# diff-probe.net
KiCad netlist of a schematic drawn in EAGLE
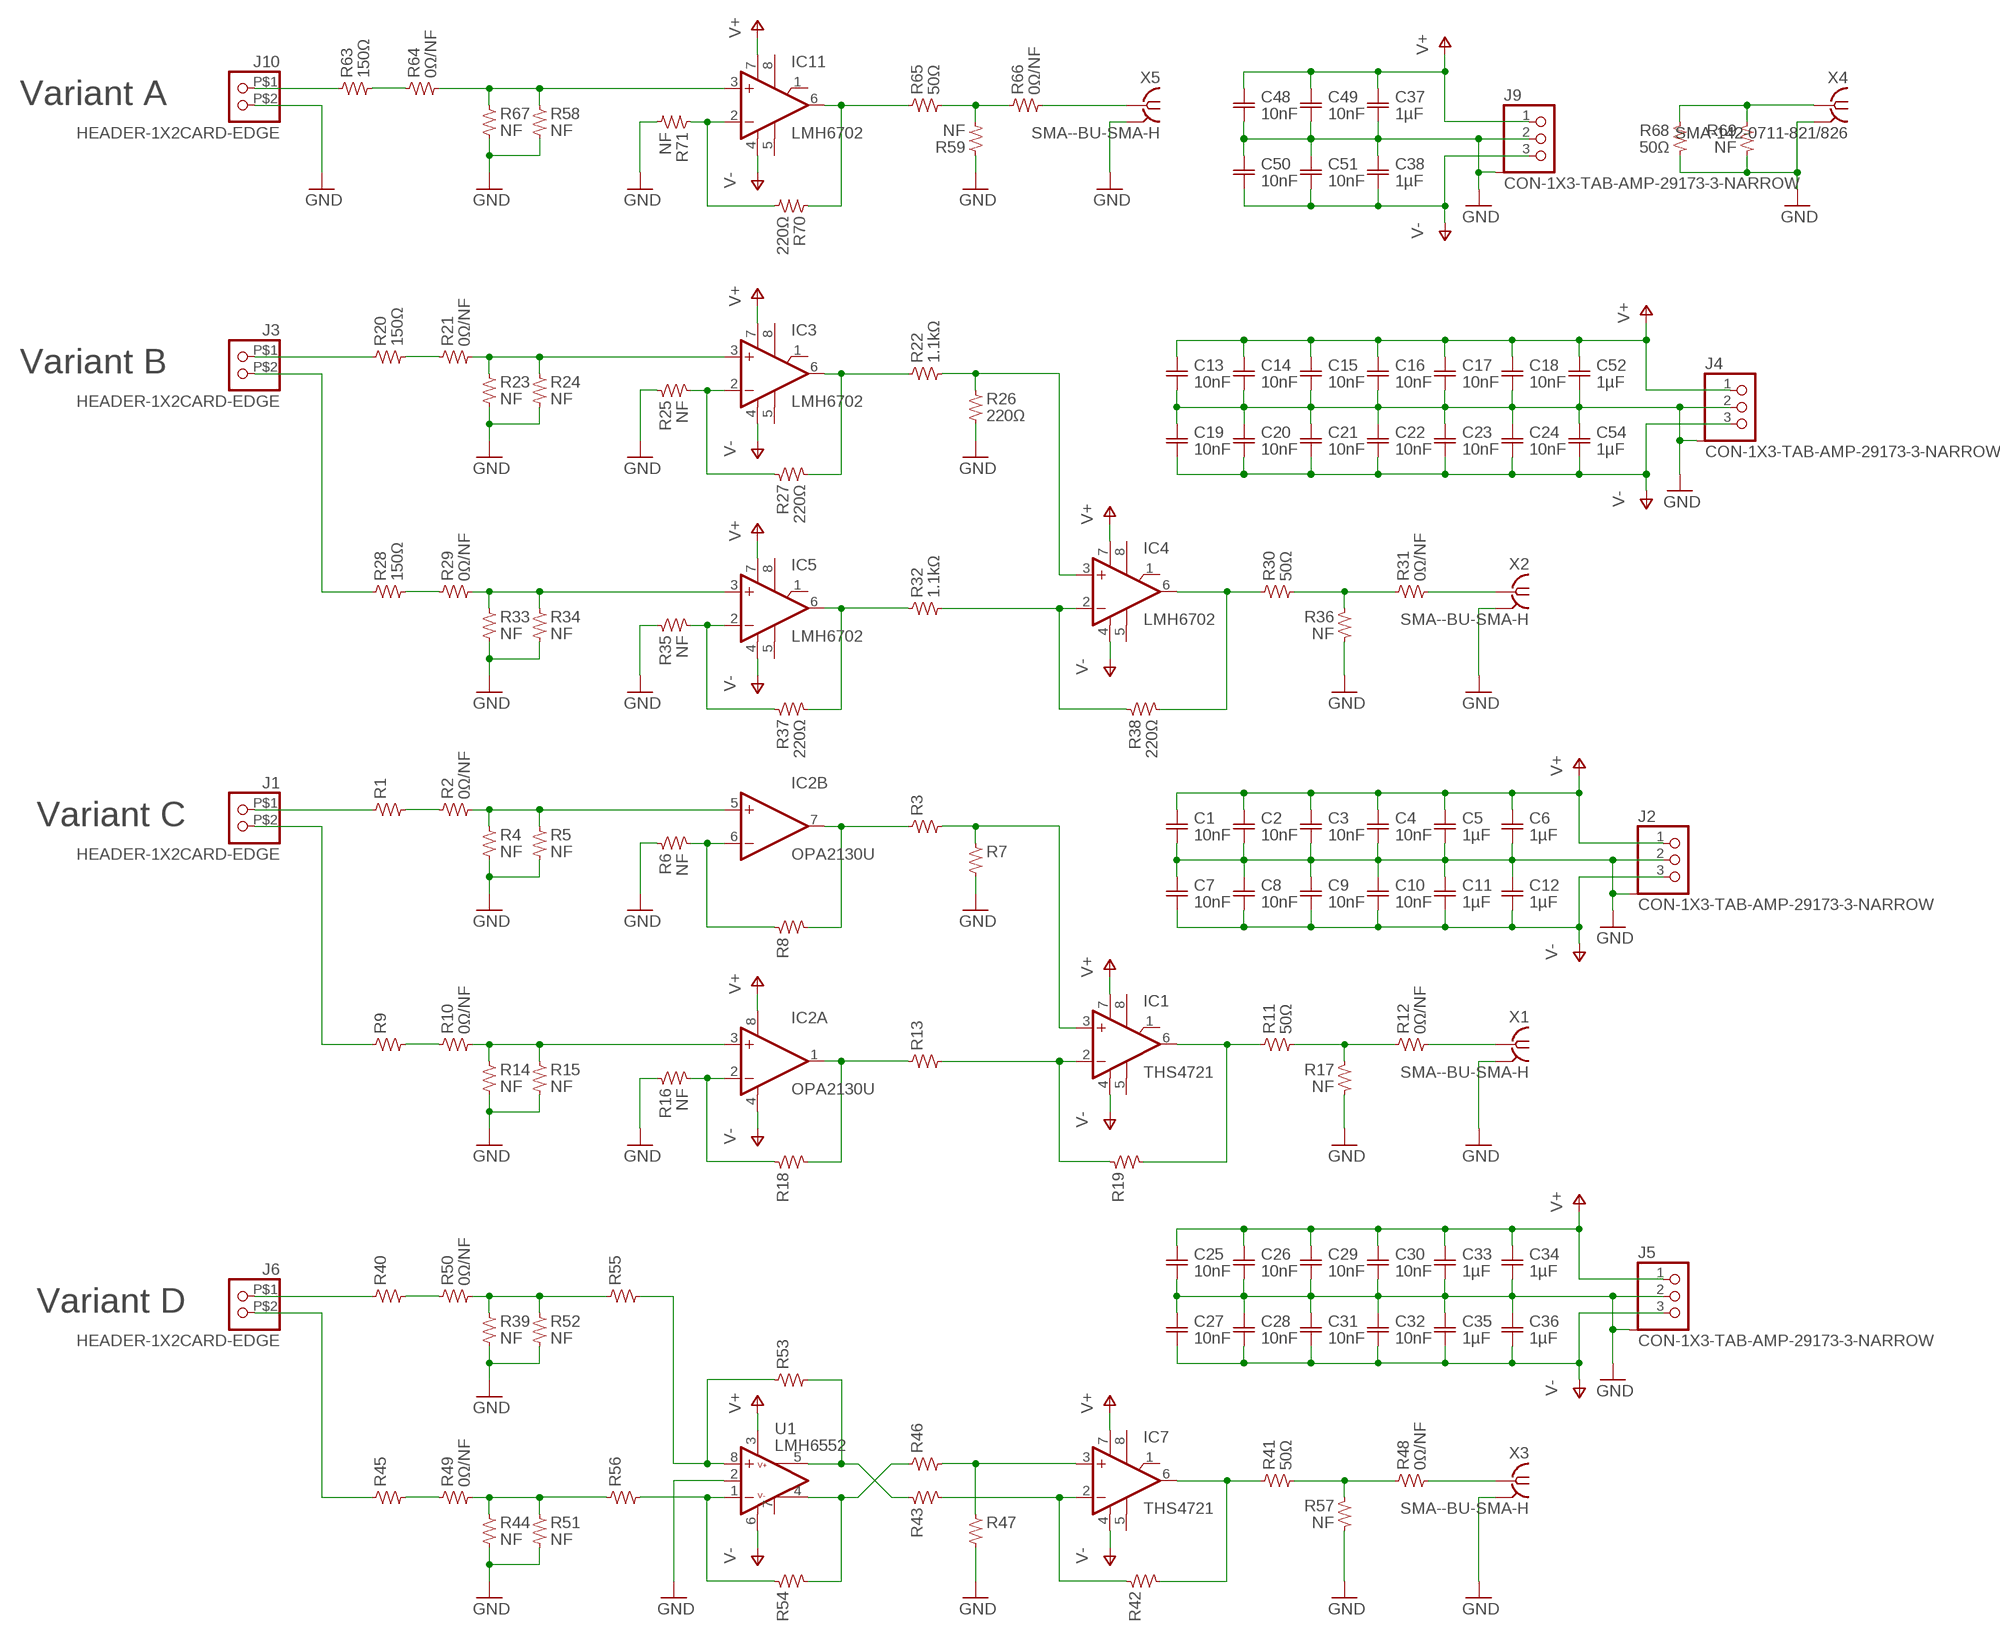
[diagram p0: schematic, sheet 1]

(export (version "E")
  (design (tool "Eeschema 10.0.6"))
  (components
    (comp (ref "C1")
      (value "10nF")
      (footprint "eagle-import:0402-SQUARE")
      (libsource (lib "eagle-import") (part "C-EU-0402-SQUARE"))
    )
    (comp (ref "C2")
      (value "10nF")
      (footprint "eagle-import:0402-SQUARE")
      (libsource (lib "eagle-import") (part "C-EU-0402-SQUARE"))
    )
    (comp (ref "C3")
      (value "10nF")
      (footprint "eagle-import:0402-SQUARE")
      (libsource (lib "eagle-import") (part "C-EU-0402-SQUARE"))
    )
    (comp (ref "C4")
      (value "10nF")
      (footprint "eagle-import:0402-SQUARE")
      (libsource (lib "eagle-import") (part "C-EU-0402-SQUARE"))
    )
    (comp (ref "C5")
      (value "1µF")
      (footprint "eagle-import:0603-SQUARE")
      (libsource (lib "eagle-import") (part "C-EU-0603-SQUARE"))
    )
    (comp (ref "C6")
      (value "1µF")
      (footprint "eagle-import:0603-SQUARE")
      (libsource (lib "eagle-import") (part "C-EU-0603-SQUARE"))
    )
    (comp (ref "C7")
      (value "10nF")
      (footprint "eagle-import:0402-SQUARE")
      (libsource (lib "eagle-import") (part "C-EU-0402-SQUARE"))
    )
    (comp (ref "C8")
      (value "10nF")
      (footprint "eagle-import:0402-SQUARE")
      (libsource (lib "eagle-import") (part "C-EU-0402-SQUARE"))
    )
    (comp (ref "C9")
      (value "10nF")
      (footprint "eagle-import:0402-SQUARE")
      (libsource (lib "eagle-import") (part "C-EU-0402-SQUARE"))
    )
    (comp (ref "C10")
      (value "10nF")
      (footprint "eagle-import:0402-SQUARE")
      (libsource (lib "eagle-import") (part "C-EU-0402-SQUARE"))
    )
    (comp (ref "C11")
      (value "1µF")
      (footprint "eagle-import:0603-SQUARE")
      (libsource (lib "eagle-import") (part "C-EU-0603-SQUARE"))
    )
    (comp (ref "C12")
      (value "1µF")
      (footprint "eagle-import:0603-SQUARE")
      (libsource (lib "eagle-import") (part "C-EU-0603-SQUARE"))
    )
    (comp (ref "C13")
      (value "10nF")
      (footprint "eagle-import:0402-SQUARE")
      (libsource (lib "eagle-import") (part "C-EU-0402-SQUARE"))
    )
    (comp (ref "C14")
      (value "10nF")
      (footprint "eagle-import:0402-SQUARE")
      (libsource (lib "eagle-import") (part "C-EU-0402-SQUARE"))
    )
    (comp (ref "C15")
      (value "10nF")
      (footprint "eagle-import:0402-SQUARE")
      (libsource (lib "eagle-import") (part "C-EU-0402-SQUARE"))
    )
    (comp (ref "C16")
      (value "10nF")
      (footprint "eagle-import:0402-SQUARE")
      (libsource (lib "eagle-import") (part "C-EU-0402-SQUARE"))
    )
    (comp (ref "C17")
      (value "10nF")
      (footprint "eagle-import:0402-SQUARE")
      (libsource (lib "eagle-import") (part "C-EU-0402-SQUARE"))
    )
    (comp (ref "C18")
      (value "10nF")
      (footprint "eagle-import:0402-SQUARE")
      (libsource (lib "eagle-import") (part "C-EU-0402-SQUARE"))
    )
    (comp (ref "C19")
      (value "10nF")
      (footprint "eagle-import:0402-SQUARE")
      (libsource (lib "eagle-import") (part "C-EU-0402-SQUARE"))
    )
    (comp (ref "C20")
      (value "10nF")
      (footprint "eagle-import:0402-SQUARE")
      (libsource (lib "eagle-import") (part "C-EU-0402-SQUARE"))
    )
    (comp (ref "C21")
      (value "10nF")
      (footprint "eagle-import:0402-SQUARE")
      (libsource (lib "eagle-import") (part "C-EU-0402-SQUARE"))
    )
    (comp (ref "C22")
      (value "10nF")
      (footprint "eagle-import:0402-SQUARE")
      (libsource (lib "eagle-import") (part "C-EU-0402-SQUARE"))
    )
    (comp (ref "C23")
      (value "10nF")
      (footprint "eagle-import:0402-SQUARE")
      (libsource (lib "eagle-import") (part "C-EU-0402-SQUARE"))
    )
    (comp (ref "C24")
      (value "10nF")
      (footprint "eagle-import:0402-SQUARE")
      (libsource (lib "eagle-import") (part "C-EU-0402-SQUARE"))
    )
    (comp (ref "C25")
      (value "10nF")
      (footprint "eagle-import:0402-SQUARE")
      (libsource (lib "eagle-import") (part "C-EU-0402-SQUARE"))
    )
    (comp (ref "C26")
      (value "10nF")
      (footprint "eagle-import:0402-SQUARE")
      (libsource (lib "eagle-import") (part "C-EU-0402-SQUARE"))
    )
    (comp (ref "C27")
      (value "10nF")
      (footprint "eagle-import:0402-SQUARE")
      (libsource (lib "eagle-import") (part "C-EU-0402-SQUARE"))
    )
    (comp (ref "C28")
      (value "10nF")
      (footprint "eagle-import:0402-SQUARE")
      (libsource (lib "eagle-import") (part "C-EU-0402-SQUARE"))
    )
    (comp (ref "C29")
      (value "10nF")
      (footprint "eagle-import:0402-SQUARE")
      (libsource (lib "eagle-import") (part "C-EU-0402-SQUARE"))
    )
    (comp (ref "C30")
      (value "10nF")
      (footprint "eagle-import:0402-SQUARE")
      (libsource (lib "eagle-import") (part "C-EU-0402-SQUARE"))
    )
    (comp (ref "C31")
      (value "10nF")
      (footprint "eagle-import:0402-SQUARE")
      (libsource (lib "eagle-import") (part "C-EU-0402-SQUARE"))
    )
    (comp (ref "C32")
      (value "10nF")
      (footprint "eagle-import:0402-SQUARE")
      (libsource (lib "eagle-import") (part "C-EU-0402-SQUARE"))
    )
    (comp (ref "C33")
      (value "1µF")
      (footprint "eagle-import:0603-SQUARE")
      (libsource (lib "eagle-import") (part "C-EU-0603-SQUARE"))
    )
    (comp (ref "C34")
      (value "1µF")
      (footprint "eagle-import:0603-SQUARE")
      (libsource (lib "eagle-import") (part "C-EU-0603-SQUARE"))
    )
    (comp (ref "C35")
      (value "1µF")
      (footprint "eagle-import:0603-SQUARE")
      (libsource (lib "eagle-import") (part "C-EU-0603-SQUARE"))
    )
    (comp (ref "C36")
      (value "1µF")
      (footprint "eagle-import:0603-SQUARE")
      (libsource (lib "eagle-import") (part "C-EU-0603-SQUARE"))
    )
    (comp (ref "C37")
      (value "1µF")
      (footprint "eagle-import:0603-SQUARE")
      (libsource (lib "eagle-import") (part "C-EU-0603-SQUARE"))
    )
    (comp (ref "C38")
      (value "1µF")
      (footprint "eagle-import:0603-SQUARE")
      (libsource (lib "eagle-import") (part "C-EU-0603-SQUARE"))
    )
    (comp (ref "C48")
      (value "10nF")
      (footprint "eagle-import:0402-SQUARE")
      (libsource (lib "eagle-import") (part "C-EU-0402-SQUARE"))
    )
    (comp (ref "C49")
      (value "10nF")
      (footprint "eagle-import:0402-SQUARE")
      (libsource (lib "eagle-import") (part "C-EU-0402-SQUARE"))
    )
    (comp (ref "C50")
      (value "10nF")
      (footprint "eagle-import:0402-SQUARE")
      (libsource (lib "eagle-import") (part "C-EU-0402-SQUARE"))
    )
    (comp (ref "C51")
      (value "10nF")
      (footprint "eagle-import:0402-SQUARE")
      (libsource (lib "eagle-import") (part "C-EU-0402-SQUARE"))
    )
    (comp (ref "C52")
      (value "1µF")
      (footprint "eagle-import:0603")
      (libsource (lib "eagle-import") (part "C-EU-0603"))
    )
    (comp (ref "C54")
      (value "1µF")
      (footprint "eagle-import:0603")
      (libsource (lib "eagle-import") (part "C-EU-0603"))
    )
    (comp (ref "IC1")
      (value "THS4721")
      (footprint "eagle-import:SO08")
      (fields (field (name "MPN") "AD9631ARZ"))
      (libsource (lib "eagle-import") (part "OP-AMP-8-TI"))
    )
    (comp (ref "IC2")
      (value "OPA2130U")
      (footprint "eagle-import:SO08")
      (fields (field (name "MF") "TEXAS INSTRUMENTS") (field (name "MPN") "OPA2130UA"))
      (libsource (lib "eagle-import") (part "OPA2130U"))
    )
    (comp (ref "IC3")
      (value "LMH6702")
      (footprint "eagle-import:SO08")
      (fields (field (name "MPN") "AD9631ARZ"))
      (libsource (lib "eagle-import") (part "OP-AMP-8-TI"))
    )
    (comp (ref "IC4")
      (value "LMH6702")
      (footprint "eagle-import:SO08")
      (fields (field (name "MPN") "AD9631ARZ"))
      (libsource (lib "eagle-import") (part "OP-AMP-8-TI"))
    )
    (comp (ref "IC5")
      (value "LMH6702")
      (footprint "eagle-import:SO08")
      (fields (field (name "MPN") "AD9631ARZ"))
      (libsource (lib "eagle-import") (part "OP-AMP-8-TI"))
    )
    (comp (ref "IC7")
      (value "THS4721")
      (footprint "eagle-import:SO08")
      (fields (field (name "MPN") "AD9631ARZ"))
      (libsource (lib "eagle-import") (part "OP-AMP-8-TI"))
    )
    (comp (ref "IC11")
      (value "LMH6702")
      (footprint "eagle-import:SO08")
      (fields (field (name "MPN") "AD9631ARZ"))
      (libsource (lib "eagle-import") (part "OP-AMP-8-TI"))
    )
    (comp (ref "J1")
      (value "HEADER-1X2CARD-EDGE")
      (footprint "eagle-import:CARD_EDGE_PADS-1X2")
      (libsource (lib "eagle-import") (part "HEADER-1X2CARD-EDGE"))
    )
    (comp (ref "J2")
      (value "CON-1X3-TAB-AMP-29173-3-NARROW")
      (footprint "eagle-import:AMP-29173-3-NARROW")
      (libsource (lib "eagle-import") (part "CON-1X3-TAB-AMP-29173-3-NARROW"))
    )
    (comp (ref "J3")
      (value "HEADER-1X2CARD-EDGE")
      (footprint "eagle-import:CARD_EDGE_PADS-1X2")
      (libsource (lib "eagle-import") (part "HEADER-1X2CARD-EDGE"))
    )
    (comp (ref "J4")
      (value "CON-1X3-TAB-AMP-29173-3-NARROW")
      (footprint "eagle-import:AMP-29173-3-NARROW")
      (libsource (lib "eagle-import") (part "CON-1X3-TAB-AMP-29173-3-NARROW"))
    )
    (comp (ref "J5")
      (value "CON-1X3-TAB-AMP-29173-3-NARROW")
      (footprint "eagle-import:AMP-29173-3-NARROW")
      (libsource (lib "eagle-import") (part "CON-1X3-TAB-AMP-29173-3-NARROW"))
    )
    (comp (ref "J6")
      (value "HEADER-1X2CARD-EDGE")
      (footprint "eagle-import:CARD_EDGE_PADS-1X2")
      (libsource (lib "eagle-import") (part "HEADER-1X2CARD-EDGE"))
    )
    (comp (ref "J9")
      (value "CON-1X3-TAB-AMP-29173-3-NARROW")
      (footprint "eagle-import:AMP-29173-3-NARROW")
      (libsource (lib "eagle-import") (part "CON-1X3-TAB-AMP-29173-3-NARROW"))
    )
    (comp (ref "J10")
      (value "HEADER-1X2CARD-EDGE")
      (footprint "eagle-import:CARD_EDGE_PADS-1X2")
      (libsource (lib "eagle-import") (part "HEADER-1X2CARD-EDGE"))
    )
    (comp (ref "R1")
      (value "R-US-0402-SQUARE")
      (footprint "eagle-import:0402-SQUARE")
      (libsource (lib "eagle-import") (part "R-US-0402-SQUARE"))
    )
    (comp (ref "R2")
      (value "0Ω/NF")
      (footprint "eagle-import:0402-SQUARE")
      (libsource (lib "eagle-import") (part "R-US-0402-SQUARE"))
    )
    (comp (ref "R3")
      (value "R-US-0402-SQUARE")
      (footprint "eagle-import:0402-SQUARE")
      (libsource (lib "eagle-import") (part "R-US-0402-SQUARE"))
    )
    (comp (ref "R4")
      (value "NF")
      (footprint "eagle-import:0402-SQUARE")
      (libsource (lib "eagle-import") (part "R-US-0402-SQUARE"))
    )
    (comp (ref "R5")
      (value "NF")
      (footprint "eagle-import:0402-SQUARE")
      (libsource (lib "eagle-import") (part "R-US-0402-SQUARE"))
    )
    (comp (ref "R6")
      (value "NF")
      (footprint "eagle-import:0402-SQUARE")
      (libsource (lib "eagle-import") (part "R-US-0402-SQUARE"))
    )
    (comp (ref "R7")
      (value "R-US-0402-SQUARE")
      (footprint "eagle-import:0402-SQUARE")
      (libsource (lib "eagle-import") (part "R-US-0402-SQUARE"))
    )
    (comp (ref "R8")
      (value "R-US-0402-SQUARE")
      (footprint "eagle-import:0402-SQUARE")
      (libsource (lib "eagle-import") (part "R-US-0402-SQUARE"))
    )
    (comp (ref "R9")
      (value "R-US-0402-SQUARE")
      (footprint "eagle-import:0402-SQUARE")
      (libsource (lib "eagle-import") (part "R-US-0402-SQUARE"))
    )
    (comp (ref "R10")
      (value "0Ω/NF")
      (footprint "eagle-import:0402-SQUARE")
      (libsource (lib "eagle-import") (part "R-US-0402-SQUARE"))
    )
    (comp (ref "R11")
      (value "50Ω")
      (footprint "eagle-import:0402-SQUARE")
      (libsource (lib "eagle-import") (part "R-US-0402-SQUARE"))
    )
    (comp (ref "R12")
      (value "0Ω/NF")
      (footprint "eagle-import:0402-SQUARE")
      (libsource (lib "eagle-import") (part "R-US-0402-SQUARE"))
    )
    (comp (ref "R13")
      (value "R-US-0402-SQUARE")
      (footprint "eagle-import:0402-SQUARE")
      (libsource (lib "eagle-import") (part "R-US-0402-SQUARE"))
    )
    (comp (ref "R14")
      (value "NF")
      (footprint "eagle-import:0402-SQUARE")
      (libsource (lib "eagle-import") (part "R-US-0402-SQUARE"))
    )
    (comp (ref "R15")
      (value "NF")
      (footprint "eagle-import:0402-SQUARE")
      (libsource (lib "eagle-import") (part "R-US-0402-SQUARE"))
    )
    (comp (ref "R16")
      (value "NF")
      (footprint "eagle-import:0402-SQUARE")
      (libsource (lib "eagle-import") (part "R-US-0402-SQUARE"))
    )
    (comp (ref "R17")
      (value "NF")
      (footprint "eagle-import:0402-SQUARE")
      (libsource (lib "eagle-import") (part "R-US-0402-SQUARE"))
    )
    (comp (ref "R18")
      (value "R-US-0402-SQUARE")
      (footprint "eagle-import:0402-SQUARE")
      (libsource (lib "eagle-import") (part "R-US-0402-SQUARE"))
    )
    (comp (ref "R19")
      (value "R-US-0402-SQUARE")
      (footprint "eagle-import:0402-SQUARE")
      (libsource (lib "eagle-import") (part "R-US-0402-SQUARE"))
    )
    (comp (ref "R20")
      (value "150Ω")
      (footprint "eagle-import:0402-SQUARE")
      (libsource (lib "eagle-import") (part "R-US-0402-SQUARE"))
    )
    (comp (ref "R21")
      (value "0Ω/NF")
      (footprint "eagle-import:0402-SQUARE")
      (libsource (lib "eagle-import") (part "R-US-0402-SQUARE"))
    )
    (comp (ref "R22")
      (value "1.1kΩ")
      (footprint "eagle-import:0402-SQUARE")
      (libsource (lib "eagle-import") (part "R-US-0402-SQUARE"))
    )
    (comp (ref "R23")
      (value "NF")
      (footprint "eagle-import:0402-SQUARE")
      (libsource (lib "eagle-import") (part "R-US-0402-SQUARE"))
    )
    (comp (ref "R24")
      (value "NF")
      (footprint "eagle-import:0402-SQUARE")
      (libsource (lib "eagle-import") (part "R-US-0402-SQUARE"))
    )
    (comp (ref "R25")
      (value "NF")
      (footprint "eagle-import:0402-SQUARE")
      (libsource (lib "eagle-import") (part "R-US-0402-SQUARE"))
    )
    (comp (ref "R26")
      (value "220Ω")
      (footprint "eagle-import:0402-SQUARE")
      (libsource (lib "eagle-import") (part "R-US-0402-SQUARE"))
    )
    (comp (ref "R27")
      (value "220Ω")
      (footprint "eagle-import:0402-SQUARE")
      (libsource (lib "eagle-import") (part "R-US-0402-SQUARE"))
    )
    (comp (ref "R28")
      (value "150Ω")
      (footprint "eagle-import:0402-SQUARE")
      (libsource (lib "eagle-import") (part "R-US-0402-SQUARE"))
    )
    (comp (ref "R29")
      (value "0Ω/NF")
      (footprint "eagle-import:0402-SQUARE")
      (libsource (lib "eagle-import") (part "R-US-0402-SQUARE"))
    )
    (comp (ref "R30")
      (value "50Ω")
      (footprint "eagle-import:0402-SQUARE")
      (libsource (lib "eagle-import") (part "R-US-0402-SQUARE"))
    )
    (comp (ref "R31")
      (value "0Ω/NF")
      (footprint "eagle-import:0402-SQUARE")
      (libsource (lib "eagle-import") (part "R-US-0402-SQUARE"))
    )
    (comp (ref "R32")
      (value "1.1kΩ")
      (footprint "eagle-import:0402-SQUARE")
      (libsource (lib "eagle-import") (part "R-US-0402-SQUARE"))
    )
    (comp (ref "R33")
      (value "NF")
      (footprint "eagle-import:0402-SQUARE")
      (libsource (lib "eagle-import") (part "R-US-0402-SQUARE"))
    )
    (comp (ref "R34")
      (value "NF")
      (footprint "eagle-import:0402-SQUARE")
      (libsource (lib "eagle-import") (part "R-US-0402-SQUARE"))
    )
    (comp (ref "R35")
      (value "NF")
      (footprint "eagle-import:0402-SQUARE")
      (libsource (lib "eagle-import") (part "R-US-0402-SQUARE"))
    )
    (comp (ref "R36")
      (value "NF")
      (footprint "eagle-import:0402-SQUARE")
      (libsource (lib "eagle-import") (part "R-US-0402-SQUARE"))
    )
    (comp (ref "R37")
      (value "220Ω")
      (footprint "eagle-import:0402-SQUARE")
      (libsource (lib "eagle-import") (part "R-US-0402-SQUARE"))
    )
    (comp (ref "R38")
      (value "220Ω")
      (footprint "eagle-import:0402-SQUARE")
      (libsource (lib "eagle-import") (part "R-US-0402-SQUARE"))
    )
    (comp (ref "R39")
      (value "NF")
      (footprint "eagle-import:0402-SQUARE")
      (libsource (lib "eagle-import") (part "R-US-0402-SQUARE"))
    )
    (comp (ref "R40")
      (value "R-US-0402-SQUARE")
      (footprint "eagle-import:0402-SQUARE")
      (libsource (lib "eagle-import") (part "R-US-0402-SQUARE"))
    )
    (comp (ref "R41")
      (value "50Ω")
      (footprint "eagle-import:0402-SQUARE")
      (libsource (lib "eagle-import") (part "R-US-0402-SQUARE"))
    )
    (comp (ref "R42")
      (value "R-US-0402-SQUARE")
      (footprint "eagle-import:0402-SQUARE")
      (libsource (lib "eagle-import") (part "R-US-0402-SQUARE"))
    )
    (comp (ref "R43")
      (value "R-US-0402-SQUARE")
      (footprint "eagle-import:0402-SQUARE")
      (libsource (lib "eagle-import") (part "R-US-0402-SQUARE"))
    )
    (comp (ref "R44")
      (value "NF")
      (footprint "eagle-import:0402-SQUARE")
      (libsource (lib "eagle-import") (part "R-US-0402-SQUARE"))
    )
    (comp (ref "R45")
      (value "R-US-0402-SQUARE")
      (footprint "eagle-import:0402-SQUARE")
      (libsource (lib "eagle-import") (part "R-US-0402-SQUARE"))
    )
    (comp (ref "R46")
      (value "R-US-0402-SQUARE")
      (footprint "eagle-import:0402-SQUARE")
      (libsource (lib "eagle-import") (part "R-US-0402-SQUARE"))
    )
    (comp (ref "R47")
      (value "R-US-0402-SQUARE")
      (footprint "eagle-import:0402-SQUARE")
      (libsource (lib "eagle-import") (part "R-US-0402-SQUARE"))
    )
    (comp (ref "R48")
      (value "0Ω/NF")
      (footprint "eagle-import:0402-SQUARE")
      (libsource (lib "eagle-import") (part "R-US-0402-SQUARE"))
    )
    (comp (ref "R49")
      (value "0Ω/NF")
      (footprint "eagle-import:0402-SQUARE")
      (libsource (lib "eagle-import") (part "R-US-0402-SQUARE"))
    )
    (comp (ref "R50")
      (value "0Ω/NF")
      (footprint "eagle-import:0402-SQUARE")
      (libsource (lib "eagle-import") (part "R-US-0402-SQUARE"))
    )
    (comp (ref "R51")
      (value "NF")
      (footprint "eagle-import:0402-SQUARE")
      (libsource (lib "eagle-import") (part "R-US-0402-SQUARE"))
    )
    (comp (ref "R52")
      (value "NF")
      (footprint "eagle-import:0402-SQUARE")
      (libsource (lib "eagle-import") (part "R-US-0402-SQUARE"))
    )
    (comp (ref "R53")
      (value "R-US-0402-SQUARE")
      (footprint "eagle-import:0402-SQUARE")
      (libsource (lib "eagle-import") (part "R-US-0402-SQUARE"))
    )
    (comp (ref "R54")
      (value "R-US-0402-SQUARE")
      (footprint "eagle-import:0402-SQUARE")
      (libsource (lib "eagle-import") (part "R-US-0402-SQUARE"))
    )
    (comp (ref "R55")
      (value "R-US-0402-SQUARE")
      (footprint "eagle-import:0402-SQUARE")
      (libsource (lib "eagle-import") (part "R-US-0402-SQUARE"))
    )
    (comp (ref "R56")
      (value "R-US-0402-SQUARE")
      (footprint "eagle-import:0402-SQUARE")
      (libsource (lib "eagle-import") (part "R-US-0402-SQUARE"))
    )
    (comp (ref "R57")
      (value "NF")
      (footprint "eagle-import:0402-SQUARE")
      (libsource (lib "eagle-import") (part "R-US-0402-SQUARE"))
    )
    (comp (ref "R58")
      (value "NF")
      (footprint "eagle-import:0402-SQUARE")
      (libsource (lib "eagle-import") (part "R-US-0402-SQUARE"))
    )
    (comp (ref "R59")
      (value "NF")
      (footprint "eagle-import:0402-SQUARE")
      (libsource (lib "eagle-import") (part "R-US-0402-SQUARE"))
    )
    (comp (ref "R63")
      (value "150Ω")
      (footprint "eagle-import:0402-SQUARE")
      (libsource (lib "eagle-import") (part "R-US-0402-SQUARE"))
    )
    (comp (ref "R64")
      (value "0Ω/NF")
      (footprint "eagle-import:0402-SQUARE")
      (libsource (lib "eagle-import") (part "R-US-0402-SQUARE"))
    )
    (comp (ref "R65")
      (value "50Ω")
      (footprint "eagle-import:0402-SQUARE")
      (libsource (lib "eagle-import") (part "R-US-0402-SQUARE"))
    )
    (comp (ref "R66")
      (value "0Ω/NF")
      (footprint "eagle-import:0402-SQUARE")
      (libsource (lib "eagle-import") (part "R-US-0402-SQUARE"))
    )
    (comp (ref "R67")
      (value "NF")
      (footprint "eagle-import:0402-SQUARE")
      (libsource (lib "eagle-import") (part "R-US-0402-SQUARE"))
    )
    (comp (ref "R68")
      (value "50Ω")
      (footprint "eagle-import:0402-SQUARE")
      (libsource (lib "eagle-import") (part "R-US-0402-SQUARE"))
    )
    (comp (ref "R69")
      (value "NF")
      (footprint "eagle-import:0603-SQUARE")
      (libsource (lib "eagle-import") (part "R-US-0603-SQUARE"))
    )
    (comp (ref "R70")
      (value "220Ω")
      (footprint "eagle-import:0402-SQUARE")
      (libsource (lib "eagle-import") (part "R-US-0402-SQUARE"))
    )
    (comp (ref "R71")
      (value "NF")
      (footprint "eagle-import:0402-SQUARE")
      (libsource (lib "eagle-import") (part "R-US-0402-SQUARE"))
    )
    (comp (ref "U1")
      (value "LMH6552")
      (footprint "eagle-import:SO08")
      (libsource (lib "eagle-import") (part "LMH6552"))
    )
    (comp (ref "X1")
      (value "SMA--BU-SMA-H")
      (footprint "eagle-import:BU-SMA-H")
      (libsource (lib "eagle-import") (part "SMA--BU-SMA-H"))
    )
    (comp (ref "X2")
      (value "SMA--BU-SMA-H")
      (footprint "eagle-import:BU-SMA-H")
      (libsource (lib "eagle-import") (part "SMA--BU-SMA-H"))
    )
    (comp (ref "X3")
      (value "SMA--BU-SMA-H")
      (footprint "eagle-import:BU-SMA-H")
      (libsource (lib "eagle-import") (part "SMA--BU-SMA-H"))
    )
    (comp (ref "X4")
      (value "SMA-142-0711-821/826")
      (footprint "eagle-import:J502-ND-142-0711-821_826")
      (fields (field (name "MF") "JOHNSON COMPONENTS") (field (name "MPN") "142-0711-821"))
      (libsource (lib "eagle-import") (part "SMA-142-0711-821/826"))
    )
    (comp (ref "X5")
      (value "SMA--BU-SMA-H")
      (footprint "eagle-import:BU-SMA-H")
      (libsource (lib "eagle-import") (part "SMA--BU-SMA-H"))
    )
  )
  (nets
    (net (code "1") (name "GND") (class "Default")
      (node (ref "C1") (pin "P$2") (pinfunction "2_P$2") (pintype "passive"))
      (node (ref "C10") (pin "P$1") (pinfunction "1_P$1") (pintype "passive"))
      (node (ref "C11") (pin "1") (pinfunction "1_1") (pintype "passive"))
      (node (ref "C12") (pin "1") (pinfunction "1_1") (pintype "passive"))
      (node (ref "C13") (pin "P$2") (pinfunction "2_P$2") (pintype "passive"))
      (node (ref "C14") (pin "P$2") (pinfunction "2_P$2") (pintype "passive"))
      (node (ref "C15") (pin "P$2") (pinfunction "2_P$2") (pintype "passive"))
      (node (ref "C16") (pin "P$2") (pinfunction "2_P$2") (pintype "passive"))
      (node (ref "C17") (pin "P$2") (pinfunction "2_P$2") (pintype "passive"))
      (node (ref "C18") (pin "P$2") (pinfunction "2_P$2") (pintype "passive"))
      (node (ref "C19") (pin "P$1") (pinfunction "1_P$1") (pintype "passive"))
      (node (ref "C2") (pin "P$2") (pinfunction "2_P$2") (pintype "passive"))
      (node (ref "C20") (pin "P$1") (pinfunction "1_P$1") (pintype "passive"))
      (node (ref "C21") (pin "P$1") (pinfunction "1_P$1") (pintype "passive"))
      (node (ref "C22") (pin "P$1") (pinfunction "1_P$1") (pintype "passive"))
      (node (ref "C23") (pin "P$1") (pinfunction "1_P$1") (pintype "passive"))
      (node (ref "C24") (pin "P$1") (pinfunction "1_P$1") (pintype "passive"))
      (node (ref "C25") (pin "P$2") (pinfunction "2_P$2") (pintype "passive"))
      (node (ref "C26") (pin "P$2") (pinfunction "2_P$2") (pintype "passive"))
      (node (ref "C27") (pin "P$1") (pinfunction "1_P$1") (pintype "passive"))
      (node (ref "C28") (pin "P$1") (pinfunction "1_P$1") (pintype "passive"))
      (node (ref "C29") (pin "P$2") (pinfunction "2_P$2") (pintype "passive"))
      (node (ref "C3") (pin "P$2") (pinfunction "2_P$2") (pintype "passive"))
      (node (ref "C30") (pin "P$2") (pinfunction "2_P$2") (pintype "passive"))
      (node (ref "C31") (pin "P$1") (pinfunction "1_P$1") (pintype "passive"))
      (node (ref "C32") (pin "P$1") (pinfunction "1_P$1") (pintype "passive"))
      (node (ref "C33") (pin "2") (pinfunction "2_2") (pintype "passive"))
      (node (ref "C34") (pin "2") (pinfunction "2_2") (pintype "passive"))
      (node (ref "C35") (pin "1") (pinfunction "1_1") (pintype "passive"))
      (node (ref "C36") (pin "1") (pinfunction "1_1") (pintype "passive"))
      (node (ref "C37") (pin "2") (pinfunction "2_2") (pintype "passive"))
      (node (ref "C38") (pin "1") (pinfunction "1_1") (pintype "passive"))
      (node (ref "C4") (pin "P$2") (pinfunction "2_P$2") (pintype "passive"))
      (node (ref "C48") (pin "P$2") (pinfunction "2_P$2") (pintype "passive"))
      (node (ref "C49") (pin "P$2") (pinfunction "2_P$2") (pintype "passive"))
      (node (ref "C5") (pin "2") (pinfunction "2_2") (pintype "passive"))
      (node (ref "C50") (pin "P$1") (pinfunction "1_P$1") (pintype "passive"))
      (node (ref "C51") (pin "P$1") (pinfunction "1_P$1") (pintype "passive"))
      (node (ref "C52") (pin "2") (pinfunction "2_2") (pintype "passive"))
      (node (ref "C54") (pin "1") (pinfunction "1_1") (pintype "passive"))
      (node (ref "C6") (pin "2") (pinfunction "2_2") (pintype "passive"))
      (node (ref "C7") (pin "P$1") (pinfunction "1_P$1") (pintype "passive"))
      (node (ref "C8") (pin "P$1") (pinfunction "1_P$1") (pintype "passive"))
      (node (ref "C9") (pin "P$1") (pinfunction "1_P$1") (pintype "passive"))
      (node (ref "J10") (pin "P$2") (pinfunction "2_P$2") (pintype "passive"))
      (node (ref "J2") (pin "2") (pinfunction "2_2") (pintype "passive"))
      (node (ref "J2") (pin "P$4") (pinfunction "P$1_P$4") (pintype "bidirectional"))
      (node (ref "J2") (pin "P$5") (pinfunction "P$1_P$5") (pintype "bidirectional"))
      (node (ref "J4") (pin "2") (pinfunction "2_2") (pintype "passive"))
      (node (ref "J4") (pin "P$4") (pinfunction "P$1_P$4") (pintype "bidirectional"))
      (node (ref "J4") (pin "P$5") (pinfunction "P$1_P$5") (pintype "bidirectional"))
      (node (ref "J5") (pin "2") (pinfunction "2_2") (pintype "passive"))
      (node (ref "J5") (pin "P$4") (pinfunction "P$1_P$4") (pintype "bidirectional"))
      (node (ref "J5") (pin "P$5") (pinfunction "P$1_P$5") (pintype "bidirectional"))
      (node (ref "J9") (pin "2") (pinfunction "2_2") (pintype "passive"))
      (node (ref "J9") (pin "P$4") (pinfunction "P$1_P$4") (pintype "bidirectional"))
      (node (ref "J9") (pin "P$5") (pinfunction "P$1_P$5") (pintype "bidirectional"))
      (node (ref "R14") (pin "P$2") (pinfunction "2_P$2") (pintype "passive"))
      (node (ref "R15") (pin "P$2") (pinfunction "2_P$2") (pintype "passive"))
      (node (ref "R16") (pin "P$1") (pinfunction "1_P$1") (pintype "passive"))
      (node (ref "R17") (pin "P$2") (pinfunction "2_P$2") (pintype "passive"))
      (node (ref "R23") (pin "P$2") (pinfunction "2_P$2") (pintype "passive"))
      (node (ref "R24") (pin "P$2") (pinfunction "2_P$2") (pintype "passive"))
      (node (ref "R25") (pin "P$1") (pinfunction "1_P$1") (pintype "passive"))
      (node (ref "R26") (pin "P$2") (pinfunction "2_P$2") (pintype "passive"))
      (node (ref "R33") (pin "P$2") (pinfunction "2_P$2") (pintype "passive"))
      (node (ref "R34") (pin "P$2") (pinfunction "2_P$2") (pintype "passive"))
      (node (ref "R35") (pin "P$1") (pinfunction "1_P$1") (pintype "passive"))
      (node (ref "R36") (pin "P$2") (pinfunction "2_P$2") (pintype "passive"))
      (node (ref "R39") (pin "P$2") (pinfunction "2_P$2") (pintype "passive"))
      (node (ref "R4") (pin "P$2") (pinfunction "2_P$2") (pintype "passive"))
      (node (ref "R44") (pin "P$2") (pinfunction "2_P$2") (pintype "passive"))
      (node (ref "R47") (pin "P$2") (pinfunction "2_P$2") (pintype "passive"))
      (node (ref "R5") (pin "P$2") (pinfunction "2_P$2") (pintype "passive"))
      (node (ref "R51") (pin "P$2") (pinfunction "2_P$2") (pintype "passive"))
      (node (ref "R52") (pin "P$2") (pinfunction "2_P$2") (pintype "passive"))
      (node (ref "R57") (pin "P$2") (pinfunction "2_P$2") (pintype "passive"))
      (node (ref "R58") (pin "P$2") (pinfunction "2_P$2") (pintype "passive"))
      (node (ref "R59") (pin "P$1") (pinfunction "1_P$1") (pintype "passive"))
      (node (ref "R6") (pin "P$1") (pinfunction "1_P$1") (pintype "passive"))
      (node (ref "R67") (pin "P$2") (pinfunction "2_P$2") (pintype "passive"))
      (node (ref "R68") (pin "P$2") (pinfunction "2_P$2") (pintype "passive"))
      (node (ref "R69") (pin "2") (pinfunction "2_2") (pintype "passive"))
      (node (ref "R7") (pin "P$2") (pinfunction "2_P$2") (pintype "passive"))
      (node (ref "R71") (pin "P$2") (pinfunction "2_P$2") (pintype "passive"))
      (node (ref "U1") (pin "2") (pinfunction "VCM_2") (pintype "input"))
      (node (ref "X1") (pin "2") (pinfunction "2_2") (pintype "passive"))
      (node (ref "X1") (pin "3") (pinfunction "2_3") (pintype "passive"))
      (node (ref "X1") (pin "4") (pinfunction "2_4") (pintype "passive"))
      (node (ref "X1") (pin "5") (pinfunction "2_5") (pintype "passive"))
      (node (ref "X2") (pin "2") (pinfunction "2_2") (pintype "passive"))
      (node (ref "X2") (pin "3") (pinfunction "2_3") (pintype "passive"))
      (node (ref "X2") (pin "4") (pinfunction "2_4") (pintype "passive"))
      (node (ref "X2") (pin "5") (pinfunction "2_5") (pintype "passive"))
      (node (ref "X3") (pin "2") (pinfunction "2_2") (pintype "passive"))
      (node (ref "X3") (pin "3") (pinfunction "2_3") (pintype "passive"))
      (node (ref "X3") (pin "4") (pinfunction "2_4") (pintype "passive"))
      (node (ref "X3") (pin "5") (pinfunction "2_5") (pintype "passive"))
      (node (ref "X4") (pin "G@1") (pinfunction "2_G@1") (pintype "passive"))
      (node (ref "X4") (pin "G@2") (pinfunction "2_G@2") (pintype "passive"))
      (node (ref "X4") (pin "G@3") (pinfunction "2_G@3") (pintype "passive"))
      (node (ref "X4") (pin "G@4") (pinfunction "2_G@4") (pintype "passive"))
      (node (ref "X5") (pin "2") (pinfunction "2_2") (pintype "passive"))
      (node (ref "X5") (pin "3") (pinfunction "2_3") (pintype "passive"))
      (node (ref "X5") (pin "4") (pinfunction "2_4") (pintype "passive"))
      (node (ref "X5") (pin "5") (pinfunction "2_5") (pintype "passive"))
    )
    (net (code "2") (name "Net-(IC1-+IN)") (class "Default")
      (node (ref "IC1") (pin "3") (pinfunction "+IN_3") (pintype "input"))
      (node (ref "R3") (pin "P$2") (pinfunction "2_P$2") (pintype "passive"))
      (node (ref "R7") (pin "P$1") (pinfunction "1_P$1") (pintype "passive"))
    )
    (net (code "3") (name "Net-(IC1--IN)") (class "Default")
      (node (ref "IC1") (pin "2") (pinfunction "-IN_2") (pintype "input"))
      (node (ref "R13") (pin "P$2") (pinfunction "2_P$2") (pintype "passive"))
      (node (ref "R19") (pin "P$1") (pinfunction "1_P$1") (pintype "passive"))
    )
    (net (code "4") (name "Net-(IC1-OUT)") (class "Default")
      (node (ref "IC1") (pin "6") (pinfunction "OUT_6") (pintype "output"))
      (node (ref "R11") (pin "P$1") (pinfunction "1_P$1") (pintype "passive"))
      (node (ref "R19") (pin "P$2") (pinfunction "2_P$2") (pintype "passive"))
    )
    (net (code "5") (name "Net-(IC2A-+IN)") (class "Default")
      (node (ref "IC2") (pin "3") (pinfunction "+IN_3") (pintype "input"))
      (node (ref "R10") (pin "P$2") (pinfunction "2_P$2") (pintype "passive"))
      (node (ref "R14") (pin "P$1") (pinfunction "1_P$1") (pintype "passive"))
      (node (ref "R15") (pin "P$1") (pinfunction "1_P$1") (pintype "passive"))
    )
    (net (code "6") (name "Net-(IC2A--IN)") (class "Default")
      (node (ref "IC2") (pin "2") (pinfunction "-IN_2") (pintype "input"))
      (node (ref "R16") (pin "P$2") (pinfunction "2_P$2") (pintype "passive"))
      (node (ref "R18") (pin "P$1") (pinfunction "1_P$1") (pintype "passive"))
    )
    (net (code "7") (name "Net-(IC2A-OUT)") (class "Default")
      (node (ref "IC2") (pin "1") (pinfunction "OUT_1") (pintype "output"))
      (node (ref "R13") (pin "P$1") (pinfunction "1_P$1") (pintype "passive"))
      (node (ref "R18") (pin "P$2") (pinfunction "2_P$2") (pintype "passive"))
    )
    (net (code "8") (name "Net-(IC2B-+IN)") (class "Default")
      (node (ref "IC2") (pin "5") (pinfunction "+IN_5") (pintype "input"))
      (node (ref "R2") (pin "P$2") (pinfunction "2_P$2") (pintype "passive"))
      (node (ref "R4") (pin "P$1") (pinfunction "1_P$1") (pintype "passive"))
      (node (ref "R5") (pin "P$1") (pinfunction "1_P$1") (pintype "passive"))
    )
    (net (code "9") (name "Net-(IC2B--IN)") (class "Default")
      (node (ref "IC2") (pin "6") (pinfunction "-IN_6") (pintype "input"))
      (node (ref "R6") (pin "P$2") (pinfunction "2_P$2") (pintype "passive"))
      (node (ref "R8") (pin "P$1") (pinfunction "1_P$1") (pintype "passive"))
    )
    (net (code "10") (name "Net-(IC2B-OUT)") (class "Default")
      (node (ref "IC2") (pin "7") (pinfunction "OUT_7") (pintype "output"))
      (node (ref "R3") (pin "P$1") (pinfunction "1_P$1") (pintype "passive"))
      (node (ref "R8") (pin "P$2") (pinfunction "2_P$2") (pintype "passive"))
    )
    (net (code "11") (name "Net-(IC3-+IN)") (class "Default")
      (node (ref "IC3") (pin "3") (pinfunction "+IN_3") (pintype "input"))
      (node (ref "R21") (pin "P$2") (pinfunction "2_P$2") (pintype "passive"))
      (node (ref "R23") (pin "P$1") (pinfunction "1_P$1") (pintype "passive"))
      (node (ref "R24") (pin "P$1") (pinfunction "1_P$1") (pintype "passive"))
    )
    (net (code "12") (name "Net-(IC3--IN)") (class "Default")
      (node (ref "IC3") (pin "2") (pinfunction "-IN_2") (pintype "input"))
      (node (ref "R25") (pin "P$2") (pinfunction "2_P$2") (pintype "passive"))
      (node (ref "R27") (pin "P$1") (pinfunction "1_P$1") (pintype "passive"))
    )
    (net (code "13") (name "Net-(IC3-OUT)") (class "Default")
      (node (ref "IC3") (pin "6") (pinfunction "OUT_6") (pintype "output"))
      (node (ref "R22") (pin "P$1") (pinfunction "1_P$1") (pintype "passive"))
      (node (ref "R27") (pin "P$2") (pinfunction "2_P$2") (pintype "passive"))
    )
    (net (code "14") (name "Net-(IC4-+IN)") (class "Default")
      (node (ref "IC4") (pin "3") (pinfunction "+IN_3") (pintype "input"))
      (node (ref "R22") (pin "P$2") (pinfunction "2_P$2") (pintype "passive"))
      (node (ref "R26") (pin "P$1") (pinfunction "1_P$1") (pintype "passive"))
    )
    (net (code "15") (name "Net-(IC4--IN)") (class "Default")
      (node (ref "IC4") (pin "2") (pinfunction "-IN_2") (pintype "input"))
      (node (ref "R32") (pin "P$2") (pinfunction "2_P$2") (pintype "passive"))
      (node (ref "R38") (pin "P$1") (pinfunction "1_P$1") (pintype "passive"))
    )
    (net (code "16") (name "Net-(IC4-OUT)") (class "Default")
      (node (ref "IC4") (pin "6") (pinfunction "OUT_6") (pintype "output"))
      (node (ref "R30") (pin "P$1") (pinfunction "1_P$1") (pintype "passive"))
      (node (ref "R38") (pin "P$2") (pinfunction "2_P$2") (pintype "passive"))
    )
    (net (code "17") (name "Net-(IC5-+IN)") (class "Default")
      (node (ref "IC5") (pin "3") (pinfunction "+IN_3") (pintype "input"))
      (node (ref "R29") (pin "P$2") (pinfunction "2_P$2") (pintype "passive"))
      (node (ref "R33") (pin "P$1") (pinfunction "1_P$1") (pintype "passive"))
      (node (ref "R34") (pin "P$1") (pinfunction "1_P$1") (pintype "passive"))
    )
    (net (code "18") (name "Net-(IC5--IN)") (class "Default")
      (node (ref "IC5") (pin "2") (pinfunction "-IN_2") (pintype "input"))
      (node (ref "R35") (pin "P$2") (pinfunction "2_P$2") (pintype "passive"))
      (node (ref "R37") (pin "P$1") (pinfunction "1_P$1") (pintype "passive"))
    )
    (net (code "19") (name "Net-(IC5-OUT)") (class "Default")
      (node (ref "IC5") (pin "6") (pinfunction "OUT_6") (pintype "output"))
      (node (ref "R32") (pin "P$1") (pinfunction "1_P$1") (pintype "passive"))
      (node (ref "R37") (pin "P$2") (pinfunction "2_P$2") (pintype "passive"))
    )
    (net (code "20") (name "Net-(IC7-+IN)") (class "Default")
      (node (ref "IC7") (pin "3") (pinfunction "+IN_3") (pintype "input"))
      (node (ref "R46") (pin "P$2") (pinfunction "2_P$2") (pintype "passive"))
      (node (ref "R47") (pin "P$1") (pinfunction "1_P$1") (pintype "passive"))
    )
    (net (code "21") (name "Net-(IC7--IN)") (class "Default")
      (node (ref "IC7") (pin "2") (pinfunction "-IN_2") (pintype "input"))
      (node (ref "R42") (pin "P$1") (pinfunction "1_P$1") (pintype "passive"))
      (node (ref "R43") (pin "P$2") (pinfunction "2_P$2") (pintype "passive"))
    )
    (net (code "22") (name "Net-(IC7-OUT)") (class "Default")
      (node (ref "IC7") (pin "6") (pinfunction "OUT_6") (pintype "output"))
      (node (ref "R41") (pin "P$1") (pinfunction "1_P$1") (pintype "passive"))
      (node (ref "R42") (pin "P$2") (pinfunction "2_P$2") (pintype "passive"))
    )
    (net (code "23") (name "Net-(IC11-+IN)") (class "Default")
      (node (ref "IC11") (pin "3") (pinfunction "+IN_3") (pintype "input"))
      (node (ref "R58") (pin "P$1") (pinfunction "1_P$1") (pintype "passive"))
      (node (ref "R64") (pin "P$2") (pinfunction "2_P$2") (pintype "passive"))
      (node (ref "R67") (pin "P$1") (pinfunction "1_P$1") (pintype "passive"))
    )
    (net (code "24") (name "Net-(IC11--IN)") (class "Default")
      (node (ref "IC11") (pin "2") (pinfunction "-IN_2") (pintype "input"))
      (node (ref "R70") (pin "P$2") (pinfunction "2_P$2") (pintype "passive"))
      (node (ref "R71") (pin "P$1") (pinfunction "1_P$1") (pintype "passive"))
    )
    (net (code "25") (name "Net-(IC11-OUT)") (class "Default")
      (node (ref "IC11") (pin "6") (pinfunction "OUT_6") (pintype "output"))
      (node (ref "R65") (pin "P$1") (pinfunction "1_P$1") (pintype "passive"))
      (node (ref "R70") (pin "P$1") (pinfunction "1_P$1") (pintype "passive"))
    )
    (net (code "26") (name "Net-(J1-1)") (class "Default")
      (node (ref "J1") (pin "P$1") (pinfunction "1_P$1") (pintype "passive"))
      (node (ref "R1") (pin "P$1") (pinfunction "1_P$1") (pintype "passive"))
    )
    (net (code "27") (name "Net-(J1-2)") (class "Default")
      (node (ref "J1") (pin "P$2") (pinfunction "2_P$2") (pintype "passive"))
      (node (ref "R9") (pin "P$1") (pinfunction "1_P$1") (pintype "passive"))
    )
    (net (code "28") (name "Net-(J3-1)") (class "Default")
      (node (ref "J3") (pin "P$1") (pinfunction "1_P$1") (pintype "passive"))
      (node (ref "R20") (pin "P$1") (pinfunction "1_P$1") (pintype "passive"))
    )
    (net (code "29") (name "Net-(J3-2)") (class "Default")
      (node (ref "J3") (pin "P$2") (pinfunction "2_P$2") (pintype "passive"))
      (node (ref "R28") (pin "P$1") (pinfunction "1_P$1") (pintype "passive"))
    )
    (net (code "30") (name "Net-(J6-1)") (class "Default")
      (node (ref "J6") (pin "P$1") (pinfunction "1_P$1") (pintype "passive"))
      (node (ref "R40") (pin "P$1") (pinfunction "1_P$1") (pintype "passive"))
    )
    (net (code "31") (name "Net-(J6-2)") (class "Default")
      (node (ref "J6") (pin "P$2") (pinfunction "2_P$2") (pintype "passive"))
      (node (ref "R45") (pin "P$1") (pinfunction "1_P$1") (pintype "passive"))
    )
    (net (code "32") (name "Net-(J10-1)") (class "Default")
      (node (ref "J10") (pin "P$1") (pinfunction "1_P$1") (pintype "passive"))
      (node (ref "R63") (pin "P$1") (pinfunction "1_P$1") (pintype "passive"))
    )
    (net (code "33") (name "Net-(R1-2)") (class "Default")
      (node (ref "R1") (pin "P$2") (pinfunction "2_P$2") (pintype "passive"))
      (node (ref "R2") (pin "P$1") (pinfunction "1_P$1") (pintype "passive"))
    )
    (net (code "34") (name "Net-(R10-1)") (class "Default")
      (node (ref "R10") (pin "P$1") (pinfunction "1_P$1") (pintype "passive"))
      (node (ref "R9") (pin "P$2") (pinfunction "2_P$2") (pintype "passive"))
    )
    (net (code "35") (name "Net-(R11-2)") (class "Default")
      (node (ref "R11") (pin "P$2") (pinfunction "2_P$2") (pintype "passive"))
      (node (ref "R12") (pin "P$1") (pinfunction "1_P$1") (pintype "passive"))
      (node (ref "R17") (pin "P$1") (pinfunction "1_P$1") (pintype "passive"))
    )
    (net (code "36") (name "Net-(R12-2)") (class "Default")
      (node (ref "R12") (pin "P$2") (pinfunction "2_P$2") (pintype "passive"))
      (node (ref "X1") (pin "1") (pinfunction "1_1") (pintype "passive"))
    )
    (net (code "37") (name "Net-(R20-2)") (class "Default")
      (node (ref "R20") (pin "P$2") (pinfunction "2_P$2") (pintype "passive"))
      (node (ref "R21") (pin "P$1") (pinfunction "1_P$1") (pintype "passive"))
    )
    (net (code "38") (name "Net-(R28-2)") (class "Default")
      (node (ref "R28") (pin "P$2") (pinfunction "2_P$2") (pintype "passive"))
      (node (ref "R29") (pin "P$1") (pinfunction "1_P$1") (pintype "passive"))
    )
    (net (code "39") (name "Net-(R30-2)") (class "Default")
      (node (ref "R30") (pin "P$2") (pinfunction "2_P$2") (pintype "passive"))
      (node (ref "R31") (pin "P$1") (pinfunction "1_P$1") (pintype "passive"))
      (node (ref "R36") (pin "P$1") (pinfunction "1_P$1") (pintype "passive"))
    )
    (net (code "40") (name "Net-(R31-2)") (class "Default")
      (node (ref "R31") (pin "P$2") (pinfunction "2_P$2") (pintype "passive"))
      (node (ref "X2") (pin "1") (pinfunction "1_1") (pintype "passive"))
    )
    (net (code "41") (name "Net-(R39-1)") (class "Default")
      (node (ref "R39") (pin "P$1") (pinfunction "1_P$1") (pintype "passive"))
      (node (ref "R50") (pin "P$2") (pinfunction "2_P$2") (pintype "passive"))
      (node (ref "R52") (pin "P$1") (pinfunction "1_P$1") (pintype "passive"))
      (node (ref "R55") (pin "P$1") (pinfunction "1_P$1") (pintype "passive"))
    )
    (net (code "42") (name "Net-(R40-2)") (class "Default")
      (node (ref "R40") (pin "P$2") (pinfunction "2_P$2") (pintype "passive"))
      (node (ref "R50") (pin "P$1") (pinfunction "1_P$1") (pintype "passive"))
    )
    (net (code "43") (name "Net-(R41-2)") (class "Default")
      (node (ref "R41") (pin "P$2") (pinfunction "2_P$2") (pintype "passive"))
      (node (ref "R48") (pin "P$1") (pinfunction "1_P$1") (pintype "passive"))
      (node (ref "R57") (pin "P$1") (pinfunction "1_P$1") (pintype "passive"))
    )
    (net (code "44") (name "Net-(R43-1)") (class "Default")
      (node (ref "R43") (pin "P$1") (pinfunction "1_P$1") (pintype "passive"))
      (node (ref "R53") (pin "P$2") (pinfunction "2_P$2") (pintype "passive"))
      (node (ref "U1") (pin "5") (pinfunction "-OUT_5") (pintype "output"))
    )
    (net (code "45") (name "Net-(R44-1)") (class "Default")
      (node (ref "R44") (pin "P$1") (pinfunction "1_P$1") (pintype "passive"))
      (node (ref "R49") (pin "P$2") (pinfunction "2_P$2") (pintype "passive"))
      (node (ref "R51") (pin "P$1") (pinfunction "1_P$1") (pintype "passive"))
      (node (ref "R56") (pin "P$1") (pinfunction "1_P$1") (pintype "passive"))
    )
    (net (code "46") (name "Net-(R45-2)") (class "Default")
      (node (ref "R45") (pin "P$2") (pinfunction "2_P$2") (pintype "passive"))
      (node (ref "R49") (pin "P$1") (pinfunction "1_P$1") (pintype "passive"))
    )
    (net (code "47") (name "Net-(R46-1)") (class "Default")
      (node (ref "R46") (pin "P$1") (pinfunction "1_P$1") (pintype "passive"))
      (node (ref "R54") (pin "P$2") (pinfunction "2_P$2") (pintype "passive"))
      (node (ref "U1") (pin "4") (pinfunction "+OUT_4") (pintype "output"))
    )
    (net (code "48") (name "Net-(R48-2)") (class "Default")
      (node (ref "R48") (pin "P$2") (pinfunction "2_P$2") (pintype "passive"))
      (node (ref "X3") (pin "1") (pinfunction "1_1") (pintype "passive"))
    )
    (net (code "49") (name "Net-(R53-1)") (class "Default")
      (node (ref "R53") (pin "P$1") (pinfunction "1_P$1") (pintype "passive"))
      (node (ref "R55") (pin "P$2") (pinfunction "2_P$2") (pintype "passive"))
      (node (ref "U1") (pin "8") (pinfunction "+IN_8") (pintype "input"))
    )
    (net (code "50") (name "Net-(R54-1)") (class "Default")
      (node (ref "R54") (pin "P$1") (pinfunction "1_P$1") (pintype "passive"))
      (node (ref "R56") (pin "P$2") (pinfunction "2_P$2") (pintype "passive"))
      (node (ref "U1") (pin "1") (pinfunction "-IN_1") (pintype "input"))
    )
    (net (code "51") (name "Net-(R59-2)") (class "Default")
      (node (ref "R59") (pin "P$2") (pinfunction "2_P$2") (pintype "passive"))
      (node (ref "R65") (pin "P$2") (pinfunction "2_P$2") (pintype "passive"))
      (node (ref "R66") (pin "P$1") (pinfunction "1_P$1") (pintype "passive"))
    )
    (net (code "52") (name "Net-(R63-2)") (class "Default")
      (node (ref "R63") (pin "P$2") (pinfunction "2_P$2") (pintype "passive"))
      (node (ref "R64") (pin "P$1") (pinfunction "1_P$1") (pintype "passive"))
    )
    (net (code "53") (name "Net-(R66-2)") (class "Default")
      (node (ref "R66") (pin "P$2") (pinfunction "2_P$2") (pintype "passive"))
      (node (ref "X5") (pin "1") (pinfunction "1_1") (pintype "passive"))
    )
    (net (code "54") (name "Net-(R68-1)") (class "Default")
      (node (ref "R68") (pin "P$1") (pinfunction "1_P$1") (pintype "passive"))
      (node (ref "R69") (pin "1") (pinfunction "1_1") (pintype "passive"))
      (node (ref "X4") (pin "1") (pinfunction "1_1") (pintype "passive"))
    )
    (net (code "55") (name "V+") (class "Default")
      (node (ref "C1") (pin "P$1") (pinfunction "1_P$1") (pintype "passive"))
      (node (ref "C13") (pin "P$1") (pinfunction "1_P$1") (pintype "passive"))
      (node (ref "C14") (pin "P$1") (pinfunction "1_P$1") (pintype "passive"))
      (node (ref "C15") (pin "P$1") (pinfunction "1_P$1") (pintype "passive"))
      (node (ref "C16") (pin "P$1") (pinfunction "1_P$1") (pintype "passive"))
      (node (ref "C17") (pin "P$1") (pinfunction "1_P$1") (pintype "passive"))
      (node (ref "C18") (pin "P$1") (pinfunction "1_P$1") (pintype "passive"))
      (node (ref "C2") (pin "P$1") (pinfunction "1_P$1") (pintype "passive"))
      (node (ref "C25") (pin "P$1") (pinfunction "1_P$1") (pintype "passive"))
      (node (ref "C26") (pin "P$1") (pinfunction "1_P$1") (pintype "passive"))
      (node (ref "C29") (pin "P$1") (pinfunction "1_P$1") (pintype "passive"))
      (node (ref "C3") (pin "P$1") (pinfunction "1_P$1") (pintype "passive"))
      (node (ref "C30") (pin "P$1") (pinfunction "1_P$1") (pintype "passive"))
      (node (ref "C33") (pin "1") (pinfunction "1_1") (pintype "passive"))
      (node (ref "C34") (pin "1") (pinfunction "1_1") (pintype "passive"))
      (node (ref "C37") (pin "1") (pinfunction "1_1") (pintype "passive"))
      (node (ref "C4") (pin "P$1") (pinfunction "1_P$1") (pintype "passive"))
      (node (ref "C48") (pin "P$1") (pinfunction "1_P$1") (pintype "passive"))
      (node (ref "C49") (pin "P$1") (pinfunction "1_P$1") (pintype "passive"))
      (node (ref "C5") (pin "1") (pinfunction "1_1") (pintype "passive"))
      (node (ref "C52") (pin "1") (pinfunction "1_1") (pintype "passive"))
      (node (ref "C6") (pin "1") (pinfunction "1_1") (pintype "passive"))
      (node (ref "IC1") (pin "7") (pinfunction "+VS1_7") (pintype "power_in"))
      (node (ref "IC11") (pin "7") (pinfunction "+VS1_7") (pintype "power_in"))
      (node (ref "IC2") (pin "8") (pinfunction "V+_8") (pintype "power_in"))
      (node (ref "IC3") (pin "7") (pinfunction "+VS1_7") (pintype "power_in"))
      (node (ref "IC4") (pin "7") (pinfunction "+VS1_7") (pintype "power_in"))
      (node (ref "IC5") (pin "7") (pinfunction "+VS1_7") (pintype "power_in"))
      (node (ref "IC7") (pin "7") (pinfunction "+VS1_7") (pintype "power_in"))
      (node (ref "J2") (pin "1") (pinfunction "1_1") (pintype "passive"))
      (node (ref "J4") (pin "1") (pinfunction "1_1") (pintype "passive"))
      (node (ref "J5") (pin "1") (pinfunction "1_1") (pintype "passive"))
      (node (ref "J9") (pin "1") (pinfunction "1_1") (pintype "passive"))
      (node (ref "U1") (pin "3") (pinfunction "V+_3") (pintype "power_in"))
    )
    (net (code "56") (name "V-") (class "Default")
      (node (ref "C10") (pin "P$2") (pinfunction "2_P$2") (pintype "passive"))
      (node (ref "C11") (pin "2") (pinfunction "2_2") (pintype "passive"))
      (node (ref "C12") (pin "2") (pinfunction "2_2") (pintype "passive"))
      (node (ref "C19") (pin "P$2") (pinfunction "2_P$2") (pintype "passive"))
      (node (ref "C20") (pin "P$2") (pinfunction "2_P$2") (pintype "passive"))
      (node (ref "C21") (pin "P$2") (pinfunction "2_P$2") (pintype "passive"))
      (node (ref "C22") (pin "P$2") (pinfunction "2_P$2") (pintype "passive"))
      (node (ref "C23") (pin "P$2") (pinfunction "2_P$2") (pintype "passive"))
      (node (ref "C24") (pin "P$2") (pinfunction "2_P$2") (pintype "passive"))
      (node (ref "C27") (pin "P$2") (pinfunction "2_P$2") (pintype "passive"))
      (node (ref "C28") (pin "P$2") (pinfunction "2_P$2") (pintype "passive"))
      (node (ref "C31") (pin "P$2") (pinfunction "2_P$2") (pintype "passive"))
      (node (ref "C32") (pin "P$2") (pinfunction "2_P$2") (pintype "passive"))
      (node (ref "C35") (pin "2") (pinfunction "2_2") (pintype "passive"))
      (node (ref "C36") (pin "2") (pinfunction "2_2") (pintype "passive"))
      (node (ref "C38") (pin "2") (pinfunction "2_2") (pintype "passive"))
      (node (ref "C50") (pin "P$2") (pinfunction "2_P$2") (pintype "passive"))
      (node (ref "C51") (pin "P$2") (pinfunction "2_P$2") (pintype "passive"))
      (node (ref "C54") (pin "2") (pinfunction "2_2") (pintype "passive"))
      (node (ref "C7") (pin "P$2") (pinfunction "2_P$2") (pintype "passive"))
      (node (ref "C8") (pin "P$2") (pinfunction "2_P$2") (pintype "passive"))
      (node (ref "C9") (pin "P$2") (pinfunction "2_P$2") (pintype "passive"))
      (node (ref "IC1") (pin "4") (pinfunction "-VS1_4") (pintype "power_in"))
      (node (ref "IC11") (pin "4") (pinfunction "-VS1_4") (pintype "power_in"))
      (node (ref "IC2") (pin "4") (pinfunction "V-_4") (pintype "power_in"))
      (node (ref "IC3") (pin "4") (pinfunction "-VS1_4") (pintype "power_in"))
      (node (ref "IC4") (pin "4") (pinfunction "-VS1_4") (pintype "power_in"))
      (node (ref "IC5") (pin "4") (pinfunction "-VS1_4") (pintype "power_in"))
      (node (ref "IC7") (pin "4") (pinfunction "-VS1_4") (pintype "power_in"))
      (node (ref "J2") (pin "3") (pinfunction "3_3") (pintype "passive"))
      (node (ref "J4") (pin "3") (pinfunction "3_3") (pintype "passive"))
      (node (ref "J5") (pin "3") (pinfunction "3_3") (pintype "passive"))
      (node (ref "J9") (pin "3") (pinfunction "3_3") (pintype "passive"))
      (node (ref "U1") (pin "6") (pinfunction "V-_6") (pintype "power_in"))
    )
    (net (code "57") (name "unconnected-(IC1--VS2-Pad5)") (class "Default")
      (node (ref "IC1") (pin "5") (pinfunction "-VS2_5") (pintype "bidirectional"))
    )
    (net (code "58") (name "unconnected-(IC1-A-Pad8)") (class "Default")
      (node (ref "IC1") (pin "8") (pinfunction "A_8") (pintype "bidirectional"))
    )
    (net (code "59") (name "unconnected-(IC1-C-Pad1)") (class "Default")
      (node (ref "IC1") (pin "1") (pinfunction "C_1") (pintype "bidirectional"))
    )
    (net (code "60") (name "unconnected-(IC3--VS2-Pad5)") (class "Default")
      (node (ref "IC3") (pin "5") (pinfunction "-VS2_5") (pintype "bidirectional"))
    )
    (net (code "61") (name "unconnected-(IC3-A-Pad8)") (class "Default")
      (node (ref "IC3") (pin "8") (pinfunction "A_8") (pintype "bidirectional"))
    )
    (net (code "62") (name "unconnected-(IC3-C-Pad1)") (class "Default")
      (node (ref "IC3") (pin "1") (pinfunction "C_1") (pintype "bidirectional"))
    )
    (net (code "63") (name "unconnected-(IC4--VS2-Pad5)") (class "Default")
      (node (ref "IC4") (pin "5") (pinfunction "-VS2_5") (pintype "bidirectional"))
    )
    (net (code "64") (name "unconnected-(IC4-A-Pad8)") (class "Default")
      (node (ref "IC4") (pin "8") (pinfunction "A_8") (pintype "bidirectional"))
    )
    (net (code "65") (name "unconnected-(IC4-C-Pad1)") (class "Default")
      (node (ref "IC4") (pin "1") (pinfunction "C_1") (pintype "bidirectional"))
    )
    (net (code "66") (name "unconnected-(IC5--VS2-Pad5)") (class "Default")
      (node (ref "IC5") (pin "5") (pinfunction "-VS2_5") (pintype "bidirectional"))
    )
    (net (code "67") (name "unconnected-(IC5-A-Pad8)") (class "Default")
      (node (ref "IC5") (pin "8") (pinfunction "A_8") (pintype "bidirectional"))
    )
    (net (code "68") (name "unconnected-(IC5-C-Pad1)") (class "Default")
      (node (ref "IC5") (pin "1") (pinfunction "C_1") (pintype "bidirectional"))
    )
    (net (code "69") (name "unconnected-(IC7--VS2-Pad5)") (class "Default")
      (node (ref "IC7") (pin "5") (pinfunction "-VS2_5") (pintype "bidirectional"))
    )
    (net (code "70") (name "unconnected-(IC7-A-Pad8)") (class "Default")
      (node (ref "IC7") (pin "8") (pinfunction "A_8") (pintype "bidirectional"))
    )
    (net (code "71") (name "unconnected-(IC7-C-Pad1)") (class "Default")
      (node (ref "IC7") (pin "1") (pinfunction "C_1") (pintype "bidirectional"))
    )
    (net (code "72") (name "unconnected-(IC11--VS2-Pad5)") (class "Default")
      (node (ref "IC11") (pin "5") (pinfunction "-VS2_5") (pintype "bidirectional"))
    )
    (net (code "73") (name "unconnected-(IC11-A-Pad8)") (class "Default")
      (node (ref "IC11") (pin "8") (pinfunction "A_8") (pintype "bidirectional"))
    )
    (net (code "74") (name "unconnected-(IC11-C-Pad1)") (class "Default")
      (node (ref "IC11") (pin "1") (pinfunction "C_1") (pintype "bidirectional"))
    )
    (net (code "75") (name "unconnected-(U1-EN-Pad7)") (class "Default")
      (node (ref "U1") (pin "7") (pinfunction "EN_7") (pintype "output"))
    )
  )
)
